# Druga_p_ytka.net
KiCad netlist of a schematic drawn in EAGLE
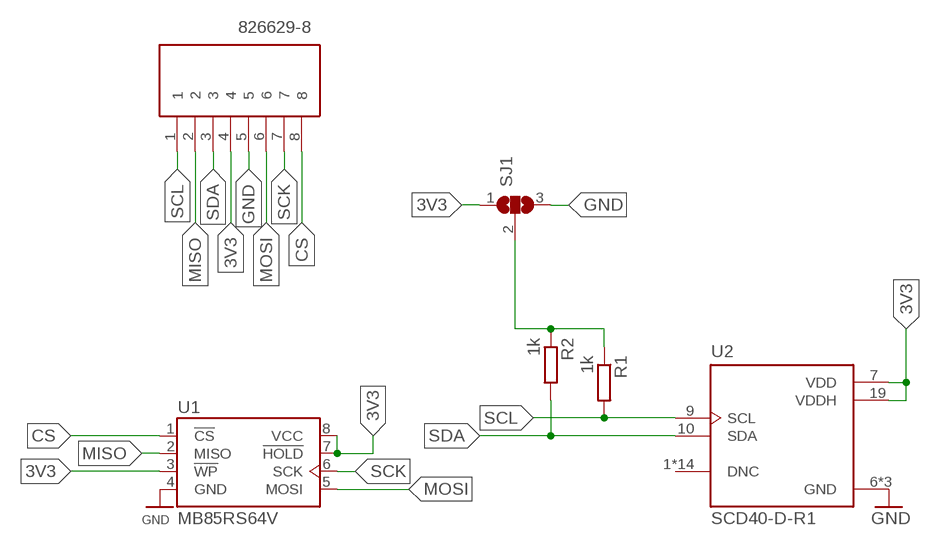
[diagram p0: schematic, sheet 1]

(export (version "E")
  (design (tool "Eeschema 10.0.6"))
  (components
    (comp (ref "J1")
      (value "826629-8")
      (footprint "eagle-import:HDRV8W63P0X254_1X8_2032X250X95")
      (fields (field (name "MOUSER_PART_NUMBER") "571-826629-8"))
      (libsource (lib "eagle-import") (part "826629-8"))
    )
    (comp (ref "R1")
      (value "1k")
      (footprint "eagle-import:0204V")
      (libsource (lib "eagle-import") (part "R-EU_0204/2V"))
    )
    (comp (ref "R2")
      (value "1k")
      (footprint "eagle-import:0204V")
      (libsource (lib "eagle-import") (part "R-EU_0204/2V"))
    )
    (comp (ref "SJ1")
      (value "SJ2W")
      (footprint "eagle-import:SJ_2")
      (libsource (lib "eagle-import") (part "SJ2W"))
    )
    (comp (ref "U1")
      (value "MB85RS64V")
      (footprint "eagle-import:SOIC127P600X155-8_R159_68_374R15")
      (fields (field (name "MF") "Fujitsu"))
      (libsource (lib "eagle-import") (part "MB85RS64V"))
    )
    (comp (ref "U2")
      (value "SCD40-D-R1")
      (footprint "eagle-import:XDCR_SCD40-D-R1")
      (fields (field (name "MF") "Sensirion AG"))
      (libsource (lib "eagle-import") (part "SCD40-D-R1"))
    )
  )
  (nets
    (net (code "1") (name "3V3") (class "Default")
      (node (ref "J1") (pin "4") (pinfunction "4_4") (pintype "bidirectional"))
      (node (ref "SJ1") (pin "1") (pinfunction "1_1") (pintype "passive"))
      (node (ref "U1") (pin "3") (pinfunction "~{WP}_3") (pintype "input"))
      (node (ref "U1") (pin "7") (pinfunction "~{HOLD}_7") (pintype "input"))
      (node (ref "U1") (pin "8") (pinfunction "VCC_8") (pintype "power_in"))
      (node (ref "U2") (pin "19") (pinfunction "VDDH_19") (pintype "power_in"))
      (node (ref "U2") (pin "7") (pinfunction "VDD_7") (pintype "power_in"))
    )
    (net (code "2") (name "CS") (class "Default")
      (node (ref "J1") (pin "8") (pinfunction "8_8") (pintype "bidirectional"))
      (node (ref "U1") (pin "1") (pinfunction "~{CS}_1") (pintype "input"))
    )
    (net (code "3") (name "GND") (class "Default")
      (node (ref "J1") (pin "5") (pinfunction "5_5") (pintype "bidirectional"))
      (node (ref "SJ1") (pin "3") (pinfunction "3_3") (pintype "passive"))
      (node (ref "U1") (pin "4") (pinfunction "GND_4") (pintype "power_in"))
      (node (ref "U2") (pin "20") (pinfunction "GND_20") (pintype "power_in"))
      (node (ref "U2") (pin "21") (pinfunction "GND_21") (pintype "power_in"))
      (node (ref "U2") (pin "6") (pinfunction "GND_6") (pintype "power_in"))
    )
    (net (code "4") (name "MISO") (class "Default")
      (node (ref "J1") (pin "2") (pinfunction "2_2") (pintype "bidirectional"))
      (node (ref "U1") (pin "2") (pinfunction "MISO_2") (pintype "output"))
    )
    (net (code "5") (name "MOSI") (class "Default")
      (node (ref "J1") (pin "6") (pinfunction "6_6") (pintype "bidirectional"))
      (node (ref "U1") (pin "5") (pinfunction "MOSI_5") (pintype "input"))
    )
    (net (code "6") (name "Net-(R1-Pad1)") (class "Default")
      (node (ref "R1") (pin "1") (pinfunction "1_1") (pintype "passive"))
      (node (ref "R2") (pin "1") (pinfunction "1_1") (pintype "passive"))
      (node (ref "SJ1") (pin "2") (pinfunction "2_2") (pintype "passive"))
    )
    (net (code "7") (name "SCK") (class "Default")
      (node (ref "J1") (pin "7") (pinfunction "7_7") (pintype "bidirectional"))
      (node (ref "U1") (pin "6") (pinfunction "SCK_6") (pintype "input"))
    )
    (net (code "8") (name "SCL") (class "Default")
      (node (ref "J1") (pin "1") (pinfunction "1_1") (pintype "bidirectional"))
      (node (ref "R1") (pin "2") (pinfunction "2_2") (pintype "passive"))
      (node (ref "U2") (pin "9") (pinfunction "SCL_9") (pintype "input"))
    )
    (net (code "9") (name "SDA") (class "Default")
      (node (ref "J1") (pin "3") (pinfunction "3_3") (pintype "bidirectional"))
      (node (ref "R2") (pin "2") (pinfunction "2_2") (pintype "passive"))
      (node (ref "U2") (pin "10") (pinfunction "SDA_10") (pintype "bidirectional"))
    )
    (net (code "10") (name "unconnected-(U2-DNC-Pad1)") (class "Default")
      (node (ref "U2") (pin "1") (pinfunction "DNC_1") (pintype "no_connect"))
    )
    (net (code "11") (name "unconnected-(U2-DNC-Pad2)") (class "Default")
      (node (ref "U2") (pin "2") (pinfunction "DNC_2") (pintype "no_connect"))
    )
    (net (code "12") (name "unconnected-(U2-DNC-Pad3)") (class "Default")
      (node (ref "U2") (pin "3") (pinfunction "DNC_3") (pintype "no_connect"))
    )
    (net (code "13") (name "unconnected-(U2-DNC-Pad4)") (class "Default")
      (node (ref "U2") (pin "4") (pinfunction "DNC_4") (pintype "no_connect"))
    )
    (net (code "14") (name "unconnected-(U2-DNC-Pad5)") (class "Default")
      (node (ref "U2") (pin "5") (pinfunction "DNC_5") (pintype "no_connect"))
    )
    (net (code "15") (name "unconnected-(U2-DNC-Pad8)") (class "Default")
      (node (ref "U2") (pin "8") (pinfunction "DNC_8") (pintype "no_connect"))
    )
    (net (code "16") (name "unconnected-(U2-DNC-Pad11)") (class "Default")
      (node (ref "U2") (pin "11") (pinfunction "DNC_11") (pintype "no_connect"))
    )
    (net (code "17") (name "unconnected-(U2-DNC-Pad12)") (class "Default")
      (node (ref "U2") (pin "12") (pinfunction "DNC_12") (pintype "no_connect"))
    )
    (net (code "18") (name "unconnected-(U2-DNC-Pad13)") (class "Default")
      (node (ref "U2") (pin "13") (pinfunction "DNC_13") (pintype "no_connect"))
    )
    (net (code "19") (name "unconnected-(U2-DNC-Pad14)") (class "Default")
      (node (ref "U2") (pin "14") (pinfunction "DNC_14") (pintype "no_connect"))
    )
    (net (code "20") (name "unconnected-(U2-DNC-Pad15)") (class "Default")
      (node (ref "U2") (pin "15") (pinfunction "DNC_15") (pintype "no_connect"))
    )
    (net (code "21") (name "unconnected-(U2-DNC-Pad16)") (class "Default")
      (node (ref "U2") (pin "16") (pinfunction "DNC_16") (pintype "no_connect"))
    )
    (net (code "22") (name "unconnected-(U2-DNC-Pad17)") (class "Default")
      (node (ref "U2") (pin "17") (pinfunction "DNC_17") (pintype "no_connect"))
    )
    (net (code "23") (name "unconnected-(U2-DNC-Pad18)") (class "Default")
      (node (ref "U2") (pin "18") (pinfunction "DNC_18") (pintype "no_connect"))
    )
  )
)
